# Endurence.net
KiCad netlist of a schematic drawn in Altium Designer
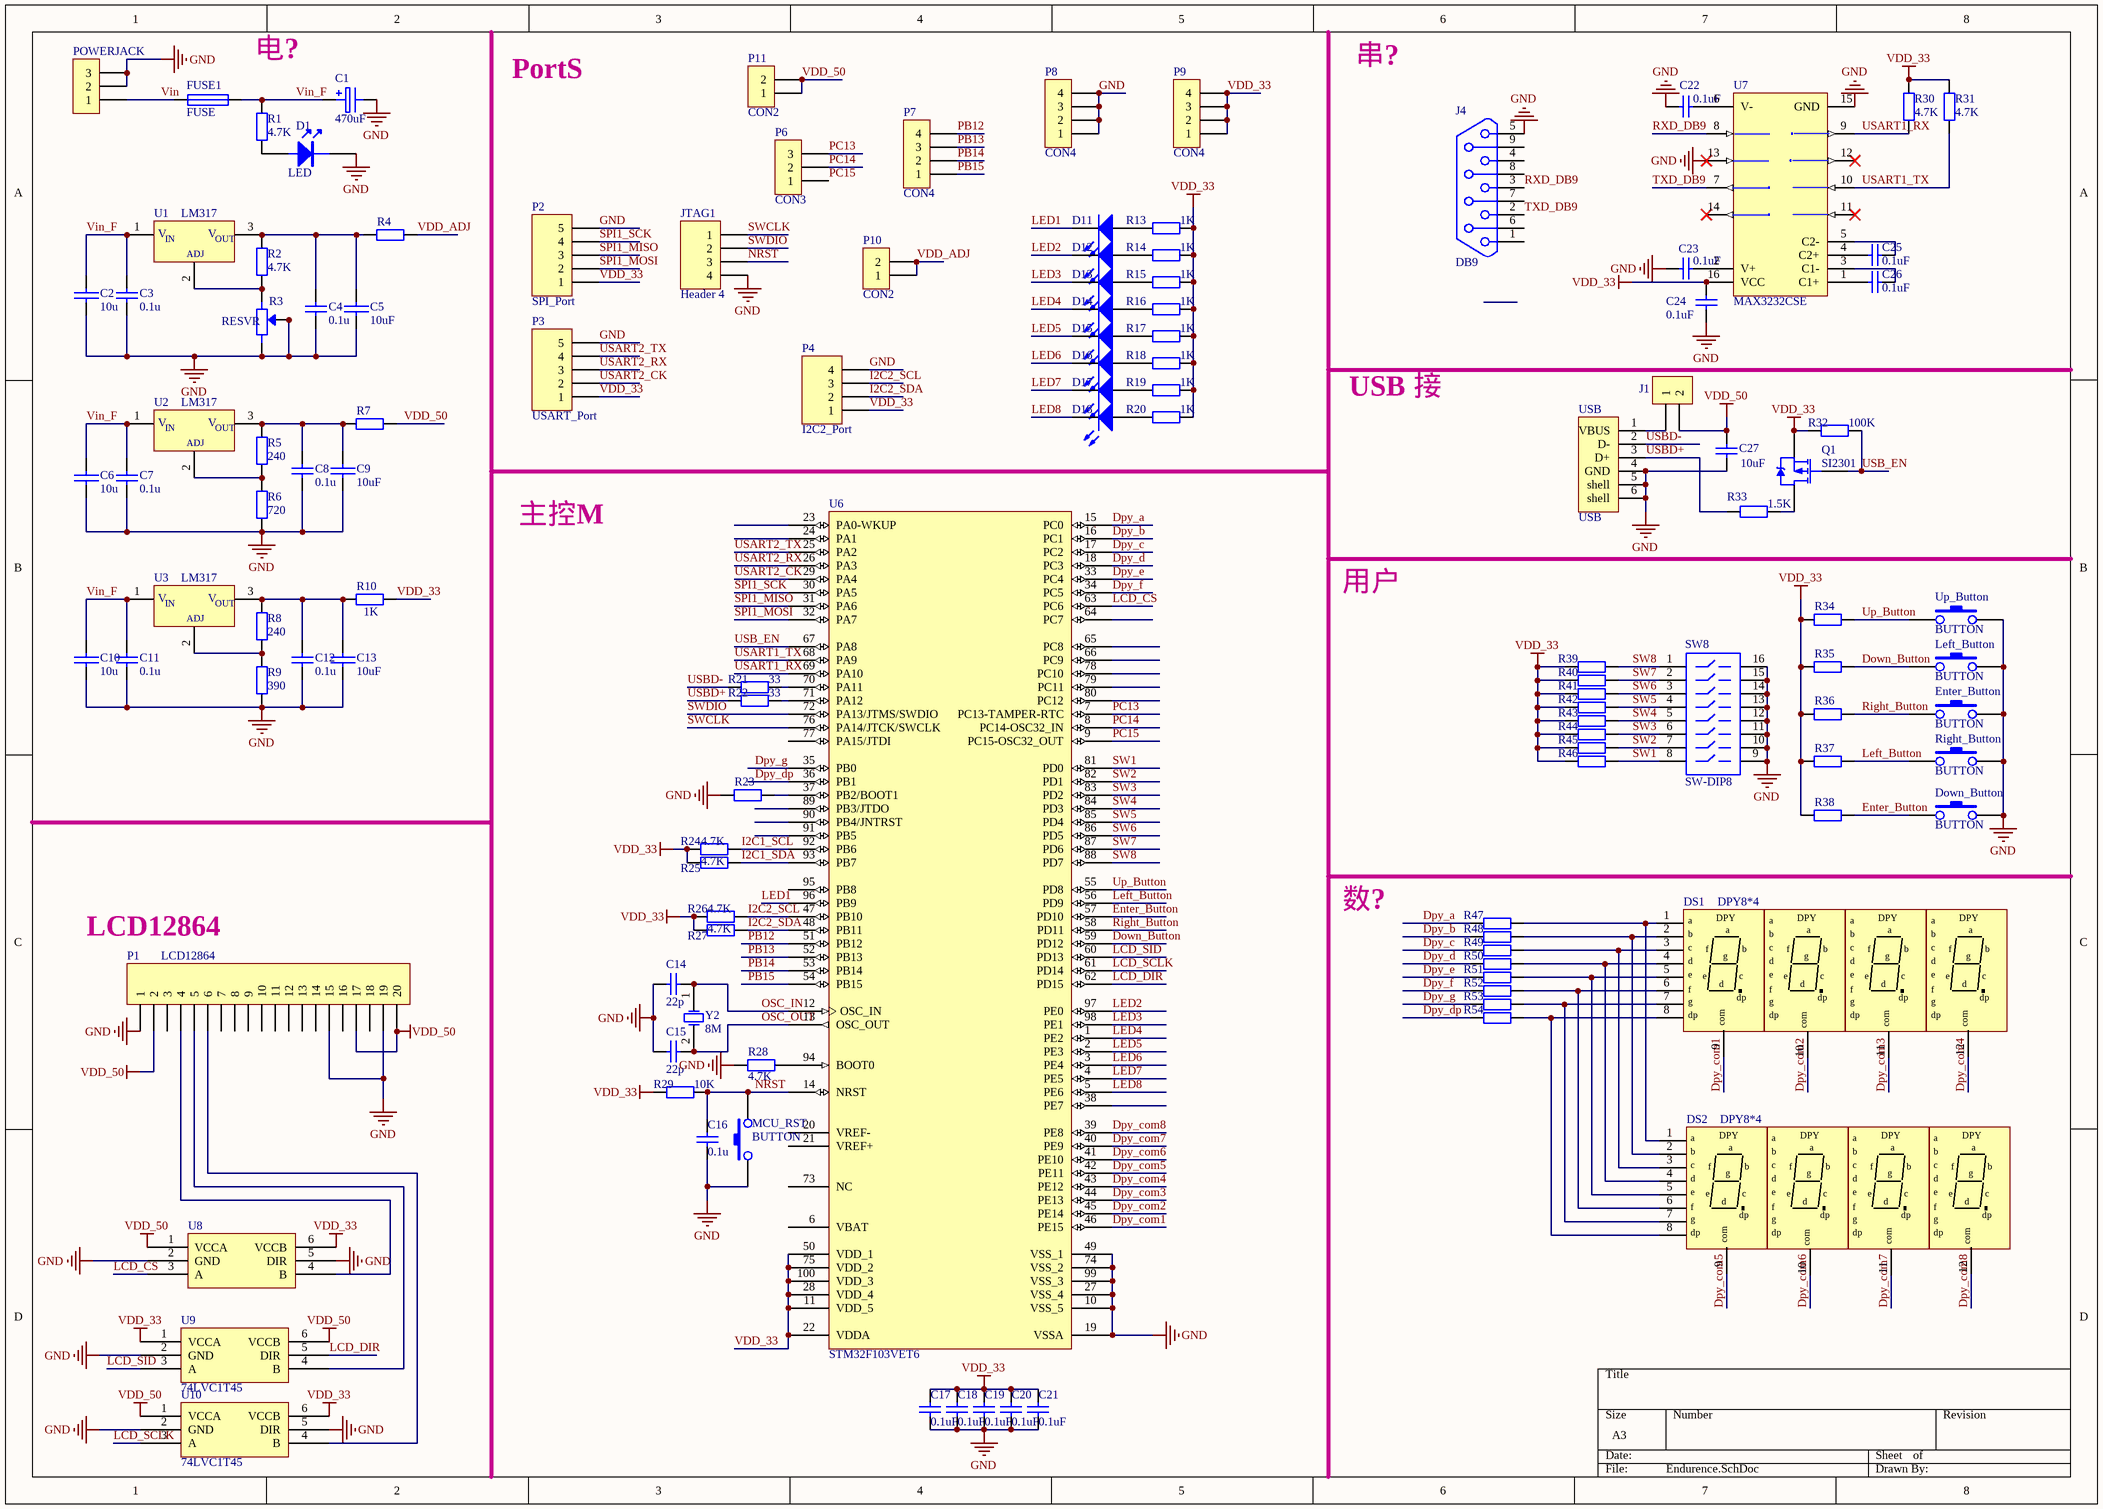
[diagram p0: Endurence.SchDoc]

(export (version "E")
  (design (tool "Eeschema 10.0.6"))
  (components
    (comp (ref "C1") (value "470uF") (footprint "MYRB.2/.4") (libsource (lib "yanschlib") (part "ELECTRO1")))
    (comp (ref "C2") (value "10u") (footprint "0805") (libsource (lib "YPF") (part "CAP")))
    (comp (ref "C3")
      (value "0.1u")
      (footprint "0805")
      (description "Capacitor")
      (fields (field (name "Comment") "0.1uF") (field (name "PUBLISHER") "Altium Limited"))
      (libsource (lib "Miscellaneous Devices") (part "Cap"))
    )
    (comp (ref "C4")
      (value "0.1u")
      (footprint "0805")
      (description "Capacitor")
      (fields (field (name "Comment") "0.1uF") (field (name "PUBLISHER") "Altium Limited"))
      (libsource (lib "Miscellaneous Devices") (part "Cap"))
    )
    (comp (ref "C5") (value "10uF") (footprint "0805") (libsource (lib "YPF") (part "CAP")))
    (comp (ref "C6") (value "10u") (footprint "0805") (libsource (lib "YPF") (part "CAP")))
    (comp (ref "C7")
      (value "0.1u")
      (footprint "0805")
      (description "Capacitor")
      (fields (field (name "Comment") "0.1uF") (field (name "PUBLISHER") "Altium Limited"))
      (libsource (lib "Miscellaneous Devices") (part "Cap"))
    )
    (comp (ref "C8")
      (value "0.1u")
      (footprint "0805")
      (description "Capacitor")
      (fields (field (name "Comment") "0.1uF") (field (name "PUBLISHER") "Altium Limited"))
      (libsource (lib "Miscellaneous Devices") (part "Cap"))
    )
    (comp (ref "C9") (value "10uF") (footprint "0805") (libsource (lib "YPF") (part "CAP")))
    (comp (ref "C10") (value "10u") (footprint "0805") (libsource (lib "YPF") (part "CAP")))
    (comp (ref "C11")
      (value "0.1u")
      (footprint "0805")
      (description "Capacitor")
      (fields (field (name "Comment") "0.1uF") (field (name "PUBLISHER") "Altium Limited"))
      (libsource (lib "Miscellaneous Devices") (part "Cap"))
    )
    (comp (ref "C12")
      (value "0.1u")
      (footprint "0805")
      (description "Capacitor")
      (fields (field (name "Comment") "0.1uF") (field (name "PUBLISHER") "Altium Limited"))
      (libsource (lib "Miscellaneous Devices") (part "Cap"))
    )
    (comp (ref "C13") (value "10uF") (footprint "0805") (libsource (lib "YPF") (part "CAP")))
    (comp (ref "C14")
      (value "22p")
      (footprint "0805")
      (description "Capacitor")
      (fields (field (name "Comment") "20pF") (field (name "PUBLISHER") "Altium Limited"))
      (libsource (lib "Miscellaneous Devices") (part "Cap"))
    )
    (comp (ref "C15")
      (value "22p")
      (footprint "0805")
      (description "Capacitor")
      (fields (field (name "Comment") "20pF") (field (name "PUBLISHER") "Altium Limited"))
      (libsource (lib "Miscellaneous Devices") (part "Cap"))
    )
    (comp (ref "C16")
      (value "0.1u")
      (footprint "0805")
      (description "Capacitor")
      (fields (field (name "Comment") "0.1uF") (field (name "PUBLISHER") "Altium Limited"))
      (libsource (lib "Miscellaneous Devices") (part "Cap"))
    )
    (comp (ref "C17")
      (value "0.1uF")
      (footprint "0805")
      (description "Capacitor")
      (fields (field (name "PUBLISHER") "Altium Limited"))
      (libsource (lib "Miscellaneous Devices") (part "Cap"))
    )
    (comp (ref "C18")
      (value "0.1uF")
      (footprint "0805")
      (description "Capacitor")
      (fields (field (name "PUBLISHER") "Altium Limited"))
      (libsource (lib "Miscellaneous Devices") (part "Cap"))
    )
    (comp (ref "C19")
      (value "0.1uF")
      (footprint "0805")
      (description "Capacitor")
      (fields (field (name "PUBLISHER") "Altium Limited"))
      (libsource (lib "Miscellaneous Devices") (part "Cap"))
    )
    (comp (ref "C20")
      (value "0.1uF")
      (footprint "0805")
      (description "Capacitor")
      (fields (field (name "PUBLISHER") "Altium Limited"))
      (libsource (lib "Miscellaneous Devices") (part "Cap"))
    )
    (comp (ref "C21")
      (value "0.1uF")
      (footprint "0805")
      (description "Capacitor")
      (fields (field (name "PUBLISHER") "Altium Limited"))
      (libsource (lib "Miscellaneous Devices") (part "Cap"))
    )
    (comp (ref "C22")
      (value "0.1uF")
      (footprint "0805")
      (description "Capacitor")
      (libsource (lib "通用元件库") (part "C"))
    )
    (comp (ref "C23")
      (value "0.1uF")
      (footprint "0805")
      (description "Capacitor")
      (libsource (lib "通用元件库") (part "C"))
    )
    (comp (ref "C24")
      (value "0.1uF")
      (footprint "0805")
      (description "Capacitor")
      (libsource (lib "通用元件库") (part "C"))
    )
    (comp (ref "C25")
      (value "0.1uF")
      (footprint "0805")
      (description "Capacitor")
      (libsource (lib "通用元件库") (part "C"))
    )
    (comp (ref "C26")
      (value "0.1uF")
      (footprint "0805")
      (description "Capacitor")
      (libsource (lib "通用元件库") (part "C"))
    )
    (comp (ref "C27")
      (value "10uF")
      (footprint "0805")
      (description "Capacitor")
      (fields (field (name "PUBLISHER") "Altium Limited"))
      (libsource (lib "Miscellaneous Devices") (part "Cap"))
    )
    (comp (ref "D1") (value "LED") (footprint "0805") (libsource (lib "FM_SCH") (part "LED")))
    (comp (ref "D11")
      (value "LED2")
      (footprint "0805")
      (description "Typical RED, GREEN, YELLOW, AMBER GaAs LED")
      (fields (field (name "PUBLISHER") "Altium Limited"))
      (libsource (lib "Miscellaneous Devices") (part "LED2"))
    )
    (comp (ref "D12")
      (value "LED2")
      (footprint "0805")
      (description "Typical RED, GREEN, YELLOW, AMBER GaAs LED")
      (fields (field (name "PUBLISHER") "Altium Limited"))
      (libsource (lib "Miscellaneous Devices") (part "LED2"))
    )
    (comp (ref "D13")
      (value "LED2")
      (footprint "0805")
      (description "Typical RED, GREEN, YELLOW, AMBER GaAs LED")
      (fields (field (name "PUBLISHER") "Altium Limited"))
      (libsource (lib "Miscellaneous Devices") (part "LED2"))
    )
    (comp (ref "D14")
      (value "LED2")
      (footprint "0805")
      (description "Typical RED, GREEN, YELLOW, AMBER GaAs LED")
      (fields (field (name "PUBLISHER") "Altium Limited"))
      (libsource (lib "Miscellaneous Devices") (part "LED2"))
    )
    (comp (ref "D15")
      (value "LED2")
      (footprint "0805")
      (description "Typical RED, GREEN, YELLOW, AMBER GaAs LED")
      (fields (field (name "PUBLISHER") "Altium Limited"))
      (libsource (lib "Miscellaneous Devices") (part "LED2"))
    )
    (comp (ref "D16")
      (value "LED2")
      (footprint "0805")
      (description "Typical RED, GREEN, YELLOW, AMBER GaAs LED")
      (fields (field (name "PUBLISHER") "Altium Limited"))
      (libsource (lib "Miscellaneous Devices") (part "LED2"))
    )
    (comp (ref "D17")
      (value "LED2")
      (footprint "0805")
      (description "Typical RED, GREEN, YELLOW, AMBER GaAs LED")
      (fields (field (name "PUBLISHER") "Altium Limited"))
      (libsource (lib "Miscellaneous Devices") (part "LED2"))
    )
    (comp (ref "D18")
      (value "LED2")
      (footprint "0805")
      (description "Typical RED, GREEN, YELLOW, AMBER GaAs LED")
      (fields (field (name "PUBLISHER") "Altium Limited"))
      (libsource (lib "Miscellaneous Devices") (part "LED2"))
    )
    (comp (ref "Down_Button")
      (value "BUTTON")
      (footprint "BUTTON-S")
      (description "乒乓球按键（压下后接通，松开自动断开），较大按键尺寸12mmX12mm选用BUTTON-L封装，较小尺寸6mmX6mm选用BUTTON-S封装")
      (libsource (lib "fm274") (part "BUTTON"))
    )
    (comp (ref "DS1")
      (value "DPY8*4")
      (footprint "DYP8*4")
      (libsource (lib "Schlib1") (part "DPY_7-SEG_DP_4"))
    )
    (comp (ref "DS2")
      (value "DPY8*4")
      (footprint "DYP8*4")
      (libsource (lib "Schlib1") (part "DPY_7-SEG_DP_4"))
    )
    (comp (ref "Enter_Button")
      (value "BUTTON")
      (footprint "BUTTON-S")
      (description "乒乓球按键（压下后接通，松开自动断开），较大按键尺寸12mmX12mm选用BUTTON-L封装，较小尺寸6mmX6mm选用BUTTON-S封装")
      (libsource (lib "fm274") (part "BUTTON"))
    )
    (comp (ref "FUSE1") (value "FUSE") (footprint "FUSE") (libsource (lib "YPF") (part "FUSE")))
    (comp (ref "J1")
      (value "CON2")
      (footprint "SIP2")
      (description "Connector")
      (libsource (lib "") (part "CON2_1"))
    )
    (comp (ref "J4")
      (value "DB9")
      (footprint "DB9")
      (description "标准DB9芯连接器，多用于串口连接，使用母型接口DB9RA/F,公型接口DB9RA/M")
      (libsource (lib "FM_SCH") (part "DB9"))
    )
    (comp (ref "JTAG1")
      (value "Header 4")
      (footprint "HDR1X4")
      (description "Header, 4-Pin")
      (fields (field (name "PUBLISHER") "Altium Limited"))
      (libsource (lib "") (part "Header 4_1"))
    )
    (comp (ref "Left_Button")
      (value "BUTTON")
      (footprint "BUTTON-S")
      (description "乒乓球按键（压下后接通，松开自动断开），较大按键尺寸12mmX12mm选用BUTTON-L封装，较小尺寸6mmX6mm选用BUTTON-S封装")
      (libsource (lib "fm274") (part "BUTTON"))
    )
    (comp (ref "MCU_RST")
      (value "BUTTON")
      (footprint "BUTTON-S")
      (description "Button")
      (libsource (lib "fm274") (part "BUTTON"))
    )
    (comp (ref "P1")
      (value "LCD12864")
      (footprint "LCD12864")
      (description "Header, 20-Pin")
      (fields (field (name "PUBLISHER") "Altium Limited"))
      (libsource (lib "Miscellaneous Connectors") (part "Header 20"))
    )
    (comp (ref "P2")
      (value "SPI_Port")
      (footprint "HDR1X5")
      (description "Header, 5-Pin")
      (fields (field (name "PUBLISHER") "Altium Limited"))
      (libsource (lib "Miscellaneous Connectors") (part "Header 5"))
    )
    (comp (ref "P3")
      (value "USART_Port")
      (footprint "HDR1X5")
      (description "Header, 5-Pin")
      (fields (field (name "PUBLISHER") "Altium Limited"))
      (libsource (lib "Miscellaneous Connectors") (part "Header 5"))
    )
    (comp (ref "P4")
      (value "I2C2_Port")
      (footprint "HDR1X4")
      (description "Header, 4-Pin")
      (fields (field (name "PUBLISHER") "Altium Limited"))
      (libsource (lib "Miscellaneous Connectors") (part "Header 4"))
    )
    (comp (ref "P6")
      (value "CON3")
      (footprint "SIP3")
      (description "Connector")
      (libsource (lib "YPF") (part "CON3"))
    )
    (comp (ref "P7")
      (value "CON4")
      (footprint "SIP4")
      (description "Connector")
      (libsource (lib "YPF") (part "CON4"))
    )
    (comp (ref "P8")
      (value "CON4")
      (footprint "SIP4")
      (description "Connector")
      (libsource (lib "YPF") (part "CON4"))
    )
    (comp (ref "P9")
      (value "CON4")
      (footprint "SIP4")
      (description "Connector")
      (libsource (lib "YPF") (part "CON4"))
    )
    (comp (ref "P10")
      (value "CON2")
      (footprint "SIP2")
      (description "Connector")
      (libsource (lib "YPF") (part "CON2"))
    )
    (comp (ref "P11")
      (value "CON2")
      (footprint "SIP2")
      (description "Connector")
      (libsource (lib "YPF") (part "CON2"))
    )
    (comp (ref "POWERJACK")
      (value "CON3")
      (footprint "POWERJACK")
      (description "Connector")
      (libsource (lib "YPF") (part "CON3"))
    )
    (comp (ref "Q1")
      (value "SI2301")
      (footprint "SOT-23-2301")
      (description "P-Channel Power MOSFET")
      (fields (field (name "PUBLISHER") "Altium Limited"))
      (libsource (lib "Miscellaneous Devices") (part "PMOS-2"))
    )
    (comp (ref "R1") (value "4.7K") (footprint "0805") (description "0805") (libsource (lib "") (part "R_2")))
    (comp (ref "R2") (value "4.7K") (footprint "0805") (description "0805") (libsource (lib "") (part "R_2")))
    (comp (ref "R3")
      (value "RESVR")
      (footprint "SIP3")
      (description "Potentiometer")
      (libsource (lib "Schlib1") (part "RESVR"))
    )
    (comp (ref "R4")
      (value "1K")
      (footprint "0805")
      (description "Resistor")
      (fields (field (name "PUBLISHER") "Altium Limited"))
      (libsource (lib "Miscellaneous Devices") (part "Res2"))
    )
    (comp (ref "R5") (value "240") (footprint "0805") (description "0805") (libsource (lib "") (part "R_2")))
    (comp (ref "R6")
      (value "720")
      (footprint "0805")
      (description "0805")
      (libsource (lib "通用元件库") (part "R"))
    )
    (comp (ref "R7")
      (value "1K")
      (footprint "0805")
      (description "Resistor")
      (fields (field (name "PUBLISHER") "Altium Limited"))
      (libsource (lib "Miscellaneous Devices") (part "Res2"))
    )
    (comp (ref "R8") (value "240") (footprint "0805") (description "0805") (libsource (lib "") (part "R_2")))
    (comp (ref "R9")
      (value "390")
      (footprint "0805")
      (description "0805")
      (libsource (lib "通用元件库") (part "R"))
    )
    (comp (ref "R10")
      (value "1K")
      (footprint "0805")
      (description "Resistor")
      (fields (field (name "PUBLISHER") "Altium Limited"))
      (libsource (lib "Miscellaneous Devices") (part "Res2"))
    )
    (comp (ref "R13")
      (value "1K")
      (footprint "0805")
      (description "Resistor")
      (fields (field (name "PUBLISHER") "Altium Limited"))
      (libsource (lib "Miscellaneous Devices") (part "Res2"))
    )
    (comp (ref "R14")
      (value "1K")
      (footprint "0805")
      (description "Resistor")
      (fields (field (name "PUBLISHER") "Altium Limited"))
      (libsource (lib "") (part "Res2_1"))
    )
    (comp (ref "R15")
      (value "1K")
      (footprint "0805")
      (description "Resistor")
      (fields (field (name "PUBLISHER") "Altium Limited"))
      (libsource (lib "Miscellaneous Devices") (part "Res2"))
    )
    (comp (ref "R16")
      (value "1K")
      (footprint "0805")
      (description "Resistor")
      (fields (field (name "PUBLISHER") "Altium Limited"))
      (libsource (lib "Miscellaneous Devices") (part "Res2"))
    )
    (comp (ref "R17")
      (value "1K")
      (footprint "0805")
      (description "Resistor")
      (fields (field (name "PUBLISHER") "Altium Limited"))
      (libsource (lib "Miscellaneous Devices") (part "Res2"))
    )
    (comp (ref "R18")
      (value "1K")
      (footprint "0805")
      (description "Resistor")
      (fields (field (name "PUBLISHER") "Altium Limited"))
      (libsource (lib "") (part "Res2_1"))
    )
    (comp (ref "R19")
      (value "1K")
      (footprint "0805")
      (description "Resistor")
      (fields (field (name "PUBLISHER") "Altium Limited"))
      (libsource (lib "Miscellaneous Devices") (part "Res2"))
    )
    (comp (ref "R20")
      (value "1K")
      (footprint "0805")
      (description "Resistor")
      (fields (field (name "PUBLISHER") "Altium Limited"))
      (libsource (lib "Miscellaneous Devices") (part "Res2"))
    )
    (comp (ref "R21")
      (value "33")
      (footprint "0805")
      (description "Resistor")
      (fields (field (name "PUBLISHER") "Altium Limited"))
      (libsource (lib "Miscellaneous Devices") (part "Res2"))
    )
    (comp (ref "R22")
      (value "33")
      (footprint "0805")
      (description "Resistor")
      (fields (field (name "PUBLISHER") "Altium Limited"))
      (libsource (lib "Miscellaneous Devices") (part "Res2"))
    )
    (comp (ref "R23")
      (value "4.7K")
      (footprint "0805")
      (description "0805")
      (libsource (lib "") (part "R_1"))
    )
    (comp (ref "R24")
      (value "4.7K")
      (footprint "0805")
      (description "0805")
      (libsource (lib "") (part "R_1"))
    )
    (comp (ref "R25")
      (value "4.7K")
      (footprint "0805")
      (description "0805")
      (libsource (lib "") (part "R_1"))
    )
    (comp (ref "R26")
      (value "4.7K")
      (footprint "0805")
      (description "0805")
      (libsource (lib "") (part "R_1"))
    )
    (comp (ref "R27")
      (value "4.7K")
      (footprint "0805")
      (description "0805")
      (libsource (lib "") (part "R_1"))
    )
    (comp (ref "R28")
      (value "4.7K")
      (footprint "0805")
      (description "0805")
      (libsource (lib "") (part "R_1"))
    )
    (comp (ref "R29")
      (value "10K")
      (footprint "0805")
      (description "Resistor")
      (fields (field (name "PUBLISHER") "Altium Limited"))
      (libsource (lib "Miscellaneous Devices") (part "Res2"))
    )
    (comp (ref "R30")
      (value "4.7K")
      (footprint "0805")
      (description "0805")
      (libsource (lib "通用元件库") (part "R"))
    )
    (comp (ref "R31")
      (value "4.7K")
      (footprint "0805")
      (description "0805")
      (libsource (lib "通用元件库") (part "R"))
    )
    (comp (ref "R32")
      (value "100K")
      (footprint "0805")
      (description "Resistor")
      (fields (field (name "PUBLISHER") "Altium Limited"))
      (libsource (lib "Miscellaneous Devices") (part "Res2"))
    )
    (comp (ref "R33")
      (value "1.5K")
      (footprint "0805")
      (description "Resistor")
      (fields (field (name "PUBLISHER") "Altium Limited"))
      (libsource (lib "Miscellaneous Devices") (part "Res2"))
    )
    (comp (ref "R34")
      (value "4.7K")
      (footprint "0805")
      (description "Resistor")
      (fields (field (name "PUBLISHER") "Altium Limited"))
      (libsource (lib "Miscellaneous Devices") (part "Res2"))
    )
    (comp (ref "R35")
      (value "4.7K")
      (footprint "0805")
      (description "Resistor")
      (fields (field (name "PUBLISHER") "Altium Limited"))
      (libsource (lib "Miscellaneous Devices") (part "Res2"))
    )
    (comp (ref "R36")
      (value "4.7K")
      (footprint "0805")
      (description "Resistor")
      (fields (field (name "PUBLISHER") "Altium Limited"))
      (libsource (lib "Miscellaneous Devices") (part "Res2"))
    )
    (comp (ref "R37")
      (value "4.7K")
      (footprint "0805")
      (description "Resistor")
      (fields (field (name "PUBLISHER") "Altium Limited"))
      (libsource (lib "Miscellaneous Devices") (part "Res2"))
    )
    (comp (ref "R38")
      (value "4.7K")
      (footprint "0805")
      (description "Resistor")
      (fields (field (name "PUBLISHER") "Altium Limited"))
      (libsource (lib "Miscellaneous Devices") (part "Res2"))
    )
    (comp (ref "R39")
      (value "4.7K")
      (footprint "0805")
      (description "Resistor")
      (fields (field (name "PUBLISHER") "Altium Limited"))
      (libsource (lib "Miscellaneous Devices") (part "Res2"))
    )
    (comp (ref "R40")
      (value "4.7K")
      (footprint "0805")
      (description "Resistor")
      (fields (field (name "PUBLISHER") "Altium Limited"))
      (libsource (lib "Miscellaneous Devices") (part "Res2"))
    )
    (comp (ref "R41")
      (value "4.7K")
      (footprint "0805")
      (description "Resistor")
      (fields (field (name "PUBLISHER") "Altium Limited"))
      (libsource (lib "Miscellaneous Devices") (part "Res2"))
    )
    (comp (ref "R42")
      (value "4.7K")
      (footprint "0805")
      (description "Resistor")
      (fields (field (name "PUBLISHER") "Altium Limited"))
      (libsource (lib "Miscellaneous Devices") (part "Res2"))
    )
    (comp (ref "R43")
      (value "4.7K")
      (footprint "0805")
      (description "Resistor")
      (fields (field (name "PUBLISHER") "Altium Limited"))
      (libsource (lib "Miscellaneous Devices") (part "Res2"))
    )
    (comp (ref "R44")
      (value "4.7K")
      (footprint "0805")
      (description "Resistor")
      (fields (field (name "PUBLISHER") "Altium Limited"))
      (libsource (lib "Miscellaneous Devices") (part "Res2"))
    )
    (comp (ref "R45")
      (value "4.7K")
      (footprint "0805")
      (description "Resistor")
      (fields (field (name "PUBLISHER") "Altium Limited"))
      (libsource (lib "Miscellaneous Devices") (part "Res2"))
    )
    (comp (ref "R46")
      (value "4.7K")
      (footprint "0805")
      (description "Resistor")
      (fields (field (name "PUBLISHER") "Altium Limited"))
      (libsource (lib "Miscellaneous Devices") (part "Res2"))
    )
    (comp (ref "R47")
      (value "1K")
      (footprint "0805")
      (description "Resistor")
      (fields (field (name "PUBLISHER") "Altium Limited"))
      (libsource (lib "Miscellaneous Devices") (part "Res2"))
    )
    (comp (ref "R48")
      (value "1K")
      (footprint "0805")
      (description "Resistor")
      (fields (field (name "PUBLISHER") "Altium Limited"))
      (libsource (lib "Miscellaneous Devices") (part "Res2"))
    )
    (comp (ref "R49")
      (value "1K")
      (footprint "0805")
      (description "Resistor")
      (fields (field (name "PUBLISHER") "Altium Limited"))
      (libsource (lib "Miscellaneous Devices") (part "Res2"))
    )
    (comp (ref "R50")
      (value "1K")
      (footprint "0805")
      (description "Resistor")
      (fields (field (name "PUBLISHER") "Altium Limited"))
      (libsource (lib "Miscellaneous Devices") (part "Res2"))
    )
    (comp (ref "R51")
      (value "1K")
      (footprint "0805")
      (description "Resistor")
      (fields (field (name "PUBLISHER") "Altium Limited"))
      (libsource (lib "Miscellaneous Devices") (part "Res2"))
    )
    (comp (ref "R52")
      (value "1K")
      (footprint "0805")
      (description "Resistor")
      (fields (field (name "PUBLISHER") "Altium Limited"))
      (libsource (lib "Miscellaneous Devices") (part "Res2"))
    )
    (comp (ref "R53")
      (value "1K")
      (footprint "0805")
      (description "Resistor")
      (fields (field (name "PUBLISHER") "Altium Limited"))
      (libsource (lib "Miscellaneous Devices") (part "Res2"))
    )
    (comp (ref "R54")
      (value "1K")
      (footprint "0805")
      (description "Resistor")
      (fields (field (name "PUBLISHER") "Altium Limited"))
      (libsource (lib "Miscellaneous Devices") (part "Res2"))
    )
    (comp (ref "Right_Button")
      (value "BUTTON")
      (footprint "BUTTON-S")
      (libsource (lib "fm274") (part "BUTTON"))
    )
    (comp (ref "SW8")
      (value "SW-DIP8")
      (footprint "SW8")
      (description "4009 Series DIP Switch, Raised actuator")
      (fields (field (name "PUBLISHER") "Altium Limited"))
      (libsource (lib "Miscellaneous Devices") (part "SW-DIP8"))
    )
    (comp (ref "U1")
      (value "LM317")
      (footprint "LM317")
      (description "3-Terminal Adjustable Positive Voltage Regulator")
      (libsource (lib "YPF") (part "LM317"))
    )
    (comp (ref "U2")
      (value "LM317")
      (footprint "LM317")
      (description "3-Terminal Adjustable Positive Voltage Regulator")
      (libsource (lib "YPF") (part "LM317"))
    )
    (comp (ref "U3")
      (value "LM317")
      (footprint "LM317")
      (description "3-Terminal Adjustable Positive Voltage Regulator")
      (libsource (lib "YPF") (part "LM317"))
    )
    (comp (ref "U6")
      (value "STM32F103VET6")
      (footprint "LQFP100")
      (description "STM32 ARM-based 32-bit MCU with 64 Kbytes Flash, 100-pin LQFP, Industrial Temperature")
      (fields (field (name "PUBLISHER") "Altium Limited"))
      (libsource (lib "YPF") (part "STM32F103V8T6"))
    )
    (comp (ref "U7")
      (value "MAX3232CSE")
      (footprint "SSOP16")
      (description "3.0V TO 5.5V, Low-Power, up to 1Mbps, True RS-232 Transceiver Using Four 0.1µF External Capacitor")
      (fields (field (name "PUBLISHER") "Altium Limited"))
      (libsource (lib "Maxim Communication Transceiver") (part "MAX3232CSE"))
    )
    (comp (ref "U8") (value "74LVC1T45") (footprint "74LVC1T45") (libsource (lib "YPF") (part "74LVC1T45")))
    (comp (ref "U9") (value "74LVC1T45") (footprint "74LVC1T45") (libsource (lib "YPF") (part "74LVC1T45")))
    (comp (ref "U10") (value "74LVC1T45") (footprint "74LVC1T45") (libsource (lib "YPF") (part "74LVC1T45")))
    (comp (ref "Up_Button")
      (value "BUTTON")
      (footprint "BUTTON-S")
      (description "乒乓球按键（压下后接通，松开自动断开），较大按键尺寸12mmX12mm选用BUTTON-L封装，较小尺寸6mmX6mm选用BUTTON-S封装")
      (libsource (lib "fm274") (part "BUTTON"))
    )
    (comp (ref "USB") (value "USB") (footprint "USB-B") (libsource (lib "USB") (part "USB")))
    (comp (ref "Y2")
      (value "8M")
      (footprint "XTAL-0.2")
      (description "Crystal Oscillator")
      (fields (field (name "PUBLISHER") "Altium Limited"))
      (libsource (lib "Miscellaneous Devices") (part "XTAL"))
    )
  )
  (nets
    (net (code "1") (name "/Down_Button") (class "Default")
      (node (ref "Left_Button") (pin "1") (pinfunction "1_1") (pintype "passive"))
      (node (ref "R35") (pin "2") (pinfunction "2_2") (pintype "passive"))
      (node (ref "U6") (pin "59") (pinfunction "PD12_59") (pintype "bidirectional"))
    )
    (net (code "2") (name "/Dpy_a") (class "Default")
      (node (ref "R47") (pin "1") (pinfunction "1_1") (pintype "passive"))
      (node (ref "U6") (pin "15") (pinfunction "PC0_15") (pintype "bidirectional"))
    )
    (net (code "3") (name "/Dpy_b") (class "Default")
      (node (ref "R48") (pin "1") (pinfunction "1_1") (pintype "passive"))
      (node (ref "U6") (pin "16") (pinfunction "PC1_16") (pintype "bidirectional"))
    )
    (net (code "4") (name "/Dpy_c") (class "Default")
      (node (ref "R49") (pin "1") (pinfunction "1_1") (pintype "passive"))
      (node (ref "U6") (pin "17") (pinfunction "PC2_17") (pintype "bidirectional"))
    )
    (net (code "5") (name "/Dpy_com1") (class "Default")
      (node (ref "DS1") (pin "9") (pinfunction "com1_9") (pintype "passive"))
      (node (ref "U6") (pin "46") (pinfunction "PE15_46") (pintype "bidirectional"))
    )
    (net (code "6") (name "/Dpy_com2") (class "Default")
      (node (ref "DS1") (pin "10") (pinfunction "com2_10") (pintype "passive"))
      (node (ref "U6") (pin "45") (pinfunction "PE14_45") (pintype "bidirectional"))
    )
    (net (code "7") (name "/Dpy_com3") (class "Default")
      (node (ref "DS1") (pin "11") (pinfunction "com3_11") (pintype "passive"))
      (node (ref "U6") (pin "44") (pinfunction "PE13_44") (pintype "bidirectional"))
    )
    (net (code "8") (name "/Dpy_com4") (class "Default")
      (node (ref "DS1") (pin "12") (pinfunction "com4_12") (pintype "passive"))
      (node (ref "U6") (pin "43") (pinfunction "PE12_43") (pintype "bidirectional"))
    )
    (net (code "9") (name "/Dpy_com5") (class "Default")
      (node (ref "DS2") (pin "9") (pinfunction "com1_9") (pintype "passive"))
      (node (ref "U6") (pin "42") (pinfunction "PE11_42") (pintype "bidirectional"))
    )
    (net (code "10") (name "/Dpy_com6") (class "Default")
      (node (ref "DS2") (pin "10") (pinfunction "com2_10") (pintype "passive"))
      (node (ref "U6") (pin "41") (pinfunction "PE10_41") (pintype "bidirectional"))
    )
    (net (code "11") (name "/Dpy_com7") (class "Default")
      (node (ref "DS2") (pin "11") (pinfunction "com3_11") (pintype "passive"))
      (node (ref "U6") (pin "40") (pinfunction "PE9_40") (pintype "bidirectional"))
    )
    (net (code "12") (name "/Dpy_com8") (class "Default")
      (node (ref "DS2") (pin "12") (pinfunction "com4_12") (pintype "passive"))
      (node (ref "U6") (pin "39") (pinfunction "PE8_39") (pintype "bidirectional"))
    )
    (net (code "13") (name "/Dpy_d") (class "Default")
      (node (ref "R50") (pin "1") (pinfunction "1_1") (pintype "passive"))
      (node (ref "U6") (pin "18") (pinfunction "PC3_18") (pintype "bidirectional"))
    )
    (net (code "14") (name "/Dpy_dp") (class "Default")
      (node (ref "R54") (pin "1") (pinfunction "1_1") (pintype "passive"))
      (node (ref "U6") (pin "36") (pinfunction "PB1_36") (pintype "bidirectional"))
    )
    (net (code "15") (name "/Dpy_e") (class "Default")
      (node (ref "R51") (pin "1") (pinfunction "1_1") (pintype "passive"))
      (node (ref "U6") (pin "33") (pinfunction "PC4_33") (pintype "bidirectional"))
    )
    (net (code "16") (name "/Dpy_f") (class "Default")
      (node (ref "R52") (pin "1") (pinfunction "1_1") (pintype "passive"))
      (node (ref "U6") (pin "34") (pinfunction "PC5_34") (pintype "bidirectional"))
    )
    (net (code "17") (name "/Dpy_g") (class "Default")
      (node (ref "R53") (pin "1") (pinfunction "1_1") (pintype "passive"))
      (node (ref "U6") (pin "35") (pinfunction "PB0_35") (pintype "bidirectional"))
    )
    (net (code "18") (name "/Enter_Button") (class "Default")
      (node (ref "Down_Button") (pin "1") (pinfunction "1_1") (pintype "passive"))
      (node (ref "R38") (pin "2") (pinfunction "2_2") (pintype "passive"))
      (node (ref "U6") (pin "57") (pinfunction "PD10_57") (pintype "bidirectional"))
    )
    (net (code "19") (name "/I2C1_SCL") (class "Default")
      (node (ref "R24") (pin "1") (pinfunction "1_1") (pintype "passive"))
      (node (ref "U6") (pin "92") (pinfunction "PB6_92") (pintype "bidirectional"))
    )
    (net (code "20") (name "/I2C1_SDA") (class "Default")
      (node (ref "R25") (pin "1") (pinfunction "1_1") (pintype "passive"))
      (node (ref "U6") (pin "93") (pinfunction "PB7_93") (pintype "bidirectional"))
    )
    (net (code "21") (name "/I2C2_SCL") (class "Default")
      (node (ref "P4") (pin "3") (pinfunction "3_3") (pintype "passive"))
      (node (ref "R26") (pin "1") (pinfunction "1_1") (pintype "passive"))
      (node (ref "U6") (pin "47") (pinfunction "PB10_47") (pintype "bidirectional"))
    )
    (net (code "22") (name "/I2C2_SDA") (class "Default")
      (node (ref "P4") (pin "2") (pinfunction "2_2") (pintype "passive"))
      (node (ref "R27") (pin "1") (pinfunction "1_1") (pintype "passive"))
      (node (ref "U6") (pin "48") (pinfunction "PB11_48") (pintype "bidirectional"))
    )
    (net (code "23") (name "/LCD_CS") (class "Default")
      (node (ref "U6") (pin "63") (pinfunction "PC6_63") (pintype "bidirectional"))
      (node (ref "U8") (pin "3") (pinfunction "A_3") (pintype "passive"))
    )
    (net (code "24") (name "/LCD_DIR") (class "Default")
      (node (ref "U6") (pin "62") (pinfunction "PD15_62") (pintype "bidirectional"))
      (node (ref "U9") (pin "5") (pinfunction "DIR_5") (pintype "passive"))
    )
    (net (code "25") (name "/LCD_SCLK") (class "Default")
      (node (ref "U10") (pin "3") (pinfunction "A_3") (pintype "passive"))
      (node (ref "U6") (pin "61") (pinfunction "PD14_61") (pintype "bidirectional"))
    )
    (net (code "26") (name "/LCD_SID") (class "Default")
      (node (ref "U6") (pin "60") (pinfunction "PD13_60") (pintype "bidirectional"))
      (node (ref "U9") (pin "3") (pinfunction "A_3") (pintype "passive"))
    )
    (net (code "27") (name "/LED1") (class "Default")
      (node (ref "D11") (pin "2") (pinfunction "K_2") (pintype "passive"))
      (node (ref "U6") (pin "96") (pinfunction "PB9_96") (pintype "bidirectional"))
    )
    (net (code "28") (name "/LED2") (class "Default")
      (node (ref "D12") (pin "2") (pinfunction "K_2") (pintype "passive"))
      (node (ref "U6") (pin "97") (pinfunction "PE0_97") (pintype "bidirectional"))
    )
    (net (code "29") (name "/LED3") (class "Default")
      (node (ref "D13") (pin "2") (pinfunction "K_2") (pintype "passive"))
      (node (ref "U6") (pin "98") (pinfunction "PE1_98") (pintype "bidirectional"))
    )
    (net (code "30") (name "/LED4") (class "Default")
      (node (ref "D14") (pin "2") (pinfunction "K_2") (pintype "passive"))
      (node (ref "U6") (pin "1") (pinfunction "PE2_1") (pintype "bidirectional"))
    )
    (net (code "31") (name "/LED5") (class "Default")
      (node (ref "D15") (pin "2") (pinfunction "K_2") (pintype "passive"))
      (node (ref "U6") (pin "2") (pinfunction "PE3_2") (pintype "bidirectional"))
    )
    (net (code "32") (name "/LED6") (class "Default")
      (node (ref "D16") (pin "2") (pinfunction "K_2") (pintype "passive"))
      (node (ref "U6") (pin "3") (pinfunction "PE4_3") (pintype "bidirectional"))
    )
    (net (code "33") (name "/LED7") (class "Default")
      (node (ref "D17") (pin "2") (pinfunction "K_2") (pintype "passive"))
      (node (ref "U6") (pin "4") (pinfunction "PE5_4") (pintype "bidirectional"))
    )
    (net (code "34") (name "/LED8") (class "Default")
      (node (ref "D18") (pin "2") (pinfunction "K_2") (pintype "passive"))
      (node (ref "U6") (pin "5") (pinfunction "PE6_5") (pintype "bidirectional"))
    )
    (net (code "35") (name "/Left_Button") (class "Default")
      (node (ref "R37") (pin "2") (pinfunction "2_2") (pintype "passive"))
      (node (ref "Right_Button") (pin "1") (pinfunction "1_1") (pintype "passive"))
      (node (ref "U6") (pin "56") (pinfunction "PD9_56") (pintype "bidirectional"))
    )
    (net (code "36") (name "/NRST") (class "Default")
      (node (ref "C16") (pin "2") (pinfunction "2_2") (pintype "passive"))
      (node (ref "JTAG1") (pin "3") (pinfunction "3_3") (pintype "passive"))
      (node (ref "MCU_RST") (pin "2") (pinfunction "2_2") (pintype "passive"))
      (node (ref "R29") (pin "2") (pinfunction "2_2") (pintype "passive"))
      (node (ref "U6") (pin "14") (pinfunction "NRST_14") (pintype "bidirectional"))
    )
    (net (code "37") (name "/OSC_IN") (class "Default")
      (node (ref "C14") (pin "1") (pinfunction "1_1") (pintype "passive"))
      (node (ref "U6") (pin "12") (pinfunction "OSC_IN_12") (pintype "input"))
      (node (ref "Y2") (pin "1") (pinfunction "OSC1_1") (pintype "passive"))
    )
    (net (code "38") (name "/OSC_OUT") (class "Default")
      (node (ref "C15") (pin "1") (pinfunction "1_1") (pintype "passive"))
      (node (ref "U6") (pin "13") (pinfunction "OSC_OUT_13") (pintype "output"))
      (node (ref "Y2") (pin "2") (pinfunction "OSC2_2") (pintype "passive"))
    )
    (net (code "39") (name "/PB12") (class "Default")
      (node (ref "P7") (pin "4") (pinfunction "4_4") (pintype "passive"))
      (node (ref "U6") (pin "51") (pinfunction "PB12_51") (pintype "bidirectional"))
    )
    (net (code "40") (name "/PB13") (class "Default")
      (node (ref "P7") (pin "3") (pinfunction "3_3") (pintype "passive"))
      (node (ref "U6") (pin "52") (pinfunction "PB13_52") (pintype "bidirectional"))
    )
    (net (code "41") (name "/PB14") (class "Default")
      (node (ref "P7") (pin "2") (pinfunction "2_2") (pintype "passive"))
      (node (ref "U6") (pin "53") (pinfunction "PB14_53") (pintype "bidirectional"))
    )
    (net (code "42") (name "/PB15") (class "Default")
      (node (ref "P7") (pin "1") (pinfunction "1_1") (pintype "passive"))
      (node (ref "U6") (pin "54") (pinfunction "PB15_54") (pintype "bidirectional"))
    )
    (net (code "43") (name "/PC13") (class "Default")
      (node (ref "P6") (pin "3") (pinfunction "3_3") (pintype "passive"))
      (node (ref "U6") (pin "7") (pinfunction "PC13-TAMPER-RTC_7") (pintype "bidirectional"))
    )
    (net (code "44") (name "/PC14") (class "Default")
      (node (ref "P6") (pin "2") (pinfunction "2_2") (pintype "passive"))
      (node (ref "U6") (pin "8") (pinfunction "PC14-OSC32_IN_8") (pintype "bidirectional"))
    )
    (net (code "45") (name "/PC15") (class "Default")
      (node (ref "P6") (pin "1") (pinfunction "1_1") (pintype "passive"))
      (node (ref "U6") (pin "9") (pinfunction "PC15-OSC32_OUT_9") (pintype "bidirectional"))
    )
    (net (code "46") (name "/RXD_DB9") (class "Default")
      (node (ref "J4") (pin "3") (pinfunction "3_3") (pintype "passive"))
      (node (ref "U7") (pin "8") (pinfunction "R2IN_8") (pintype "input"))
    )
    (net (code "47") (name "/Right_Button") (class "Default")
      (node (ref "Enter_Button") (pin "1") (pinfunction "1_1") (pintype "passive"))
      (node (ref "R36") (pin "2") (pinfunction "2_2") (pintype "passive"))
      (node (ref "U6") (pin "58") (pinfunction "PD11_58") (pintype "bidirectional"))
    )
    (net (code "48") (name "/SPI1_MISO") (class "Default")
      (node (ref "P2") (pin "3") (pinfunction "3_3") (pintype "passive"))
      (node (ref "U6") (pin "31") (pinfunction "PA6_31") (pintype "bidirectional"))
    )
    (net (code "49") (name "/SPI1_MOSI") (class "Default")
      (node (ref "P2") (pin "2") (pinfunction "2_2") (pintype "passive"))
      (node (ref "U6") (pin "32") (pinfunction "PA7_32") (pintype "bidirectional"))
    )
    (net (code "50") (name "/SPI1_SCK") (class "Default")
      (node (ref "P2") (pin "4") (pinfunction "4_4") (pintype "passive"))
      (node (ref "U6") (pin "30") (pinfunction "PA5_30") (pintype "bidirectional"))
    )
    (net (code "51") (name "/SW1") (class "Default")
      (node (ref "R46") (pin "2") (pinfunction "2_2") (pintype "passive"))
      (node (ref "SW8") (pin "8") (pinfunction "8_8") (pintype "passive"))
      (node (ref "U6") (pin "81") (pinfunction "PD0_81") (pintype "bidirectional"))
    )
    (net (code "52") (name "/SW2") (class "Default")
      (node (ref "R45") (pin "2") (pinfunction "2_2") (pintype "passive"))
      (node (ref "SW8") (pin "7") (pinfunction "7_7") (pintype "passive"))
      (node (ref "U6") (pin "82") (pinfunction "PD1_82") (pintype "bidirectional"))
    )
    (net (code "53") (name "/SW3") (class "Default")
      (node (ref "R44") (pin "2") (pinfunction "2_2") (pintype "passive"))
      (node (ref "SW8") (pin "6") (pinfunction "6_6") (pintype "passive"))
      (node (ref "U6") (pin "83") (pinfunction "PD2_83") (pintype "bidirectional"))
    )
    (net (code "54") (name "/SW4") (class "Default")
      (node (ref "R43") (pin "2") (pinfunction "2_2") (pintype "passive"))
      (node (ref "SW8") (pin "5") (pinfunction "5_5") (pintype "passive"))
      (node (ref "U6") (pin "84") (pinfunction "PD3_84") (pintype "bidirectional"))
    )
    (net (code "55") (name "/SW5") (class "Default")
      (node (ref "R42") (pin "2") (pinfunction "2_2") (pintype "passive"))
      (node (ref "SW8") (pin "4") (pinfunction "4_4") (pintype "passive"))
      (node (ref "U6") (pin "85") (pinfunction "PD4_85") (pintype "bidirectional"))
    )
    (net (code "56") (name "/SW6") (class "Default")
      (node (ref "R41") (pin "2") (pinfunction "2_2") (pintype "passive"))
      (node (ref "SW8") (pin "3") (pinfunction "3_3") (pintype "passive"))
      (node (ref "U6") (pin "86") (pinfunction "PD5_86") (pintype "bidirectional"))
    )
    (net (code "57") (name "/SW7") (class "Default")
      (node (ref "R40") (pin "2") (pinfunction "2_2") (pintype "passive"))
      (node (ref "SW8") (pin "2") (pinfunction "2_2") (pintype "passive"))
      (node (ref "U6") (pin "87") (pinfunction "PD6_87") (pintype "bidirectional"))
    )
    (net (code "58") (name "/SW8") (class "Default")
      (node (ref "R39") (pin "2") (pinfunction "2_2") (pintype "passive"))
      (node (ref "SW8") (pin "1") (pinfunction "1_1") (pintype "passive"))
      (node (ref "U6") (pin "88") (pinfunction "PD7_88") (pintype "bidirectional"))
    )
    (net (code "59") (name "/SWCLK") (class "Default")
      (node (ref "JTAG1") (pin "1") (pinfunction "1_1") (pintype "passive"))
      (node (ref "U6") (pin "76") (pinfunction "PA14/JTCK/SWCLK_76") (pintype "bidirectional"))
    )
    (net (code "60") (name "/SWDIO") (class "Default")
      (node (ref "JTAG1") (pin "2") (pinfunction "2_2") (pintype "passive"))
      (node (ref "U6") (pin "72") (pinfunction "PA13/JTMS/SWDIO_72") (pintype "bidirectional"))
    )
    (net (code "61") (name "/TXD_DB9") (class "Default")
      (node (ref "J4") (pin "2") (pinfunction "2_2") (pintype "passive"))
      (node (ref "U7") (pin "7") (pinfunction "T2OUT_7") (pintype "output"))
    )
    (net (code "62") (name "/USART1_RX") (class "Default")
      (node (ref "R30") (pin "1") (pinfunction "1_1") (pintype "passive"))
      (node (ref "U6") (pin "69") (pinfunction "PA10_69") (pintype "bidirectional"))
      (node (ref "U7") (pin "9") (pinfunction "R2OUT_9") (pintype "output"))
    )
    (net (code "63") (name "/USART1_TX") (class "Default")
      (node (ref "R31") (pin "1") (pinfunction "1_1") (pintype "passive"))
      (node (ref "U6") (pin "68") (pinfunction "PA9_68") (pintype "bidirectional"))
      (node (ref "U7") (pin "10") (pinfunction "T2IN_10") (pintype "input"))
    )
    (net (code "64") (name "/USART2_CK") (class "Default")
      (node (ref "P3") (pin "2") (pinfunction "2_2") (pintype "passive"))
      (node (ref "U6") (pin "29") (pinfunction "PA4_29") (pintype "bidirectional"))
    )
    (net (code "65") (name "/USART2_RX") (class "Default")
      (node (ref "P3") (pin "3") (pinfunction "3_3") (pintype "passive"))
      (node (ref "U6") (pin "26") (pinfunction "PA3_26") (pintype "bidirectional"))
    )
    (net (code "66") (name "/USART2_TX") (class "Default")
      (node (ref "P3") (pin "4") (pinfunction "4_4") (pintype "passive"))
      (node (ref "U6") (pin "25") (pinfunction "PA2_25") (pintype "bidirectional"))
    )
    (net (code "67") (name "/USBD+") (class "Default")
      (node (ref "R22") (pin "1") (pinfunction "1_1") (pintype "passive"))
      (node (ref "R33") (pin "1") (pinfunction "1_1") (pintype "passive"))
      (node (ref "USB") (pin "3") (pinfunction "D+_3") (pintype "passive"))
    )
    (net (code "68") (name "/USBD-") (class "Default")
      (node (ref "R21") (pin "1") (pinfunction "1_1") (pintype "passive"))
      (node (ref "USB") (pin "2") (pinfunction "D-_2") (pintype "passive"))
    )
    (net (code "69") (name "/USB_EN") (class "Default")
      (node (ref "Q1") (pin "1") (pinfunction "G_1") (pintype "passive"))
      (node (ref "R32") (pin "2") (pinfunction "2_2") (pintype "passive"))
      (node (ref "U6") (pin "67") (pinfunction "PA8_67") (pintype "bidirectional"))
    )
    (net (code "70") (name "/Up_Button") (class "Default")
      (node (ref "R34") (pin "2") (pinfunction "2_2") (pintype "passive"))
      (node (ref "U6") (pin "55") (pinfunction "PD8_55") (pintype "bidirectional"))
      (node (ref "Up_Button") (pin "1") (pinfunction "1_1") (pintype "passive"))
    )
    (net (code "71") (name "/VDD_ADJ") (class "Default")
      (node (ref "P10") (pin "1") (pinfunction "1_1") (pintype "passive"))
      (node (ref "P10") (pin "2") (pinfunction "2_2") (pintype "passive"))
      (node (ref "R4") (pin "2") (pinfunction "2_2") (pintype "passive"))
    )
    (net (code "72") (name "/Vin") (class "Default")
      (node (ref "FUSE1") (pin "1") (pinfunction "1_1") (pintype "passive"))
      (node (ref "POWERJACK") (pin "1") (pinfunction "1_1") (pintype "passive"))
    )
    (net (code "73") (name "/Vin_F") (class "Default")
      (node (ref "C1") (pin "1") (pintype "passive"))
      (node (ref "C10") (pin "1") (pinfunction "1_1") (pintype "passive"))
      (node (ref "C11") (pin "2") (pinfunction "2_2") (pintype "passive"))
      (node (ref "C2") (pin "1") (pinfunction "1_1") (pintype "passive"))
      (node (ref "C3") (pin "2") (pinfunction "2_2") (pintype "passive"))
      (node (ref "C6") (pin "1") (pinfunction "1_1") (pintype "passive"))
      (node (ref "C7") (pin "2") (pinfunction "2_2") (pintype "passive"))
      (node (ref "FUSE1") (pin "2") (pinfunction "2_2") (pintype "passive"))
      (node (ref "R1") (pin "1") (pinfunction "1_1") (pintype "passive"))
      (node (ref "U1") (pin "1") (pinfunction "VIN_1") (pintype "passive"))
      (node (ref "U2") (pin "1") (pinfunction "VIN_1") (pintype "passive"))
      (node (ref "U3") (pin "1") (pinfunction "VIN_1") (pintype "passive"))
    )
    (net (code "74") (name "GND") (class "Default")
      (node (ref "C1") (pin "2") (pintype "passive"))
      (node (ref "C10") (pin "2") (pinfunction "2_2") (pintype "passive"))
      (node (ref "C11") (pin "1") (pinfunction "1_1") (pintype "passive"))
      (node (ref "C12") (pin "1") (pinfunction "1_1") (pintype "passive"))
      (node (ref "C13") (pin "2") (pinfunction "2_2") (pintype "passive"))
      (node (ref "C14") (pin "2") (pinfunction "2_2") (pintype "passive"))
      (node (ref "C15") (pin "2") (pinfunction "2_2") (pintype "passive"))
      (node (ref "C16") (pin "1") (pinfunction "1_1") (pintype "passive"))
      (node (ref "C17") (pin "1") (pinfunction "1_1") (pintype "passive"))
      (node (ref "C18") (pin "1") (pinfunction "1_1") (pintype "passive"))
      (node (ref "C19") (pin "1") (pinfunction "1_1") (pintype "passive"))
      (node (ref "C2") (pin "2") (pinfunction "2_2") (pintype "passive"))
      (node (ref "C20") (pin "1") (pinfunction "1_1") (pintype "passive"))
      (node (ref "C21") (pin "1") (pinfunction "1_1") (pintype "passive"))
      (node (ref "C22") (pin "2") (pinfunction "2_2") (pintype "passive"))
      (node (ref "C23") (pin "2") (pinfunction "2_2") (pintype "passive"))
      (node (ref "C24") (pin "1") (pinfunction "1_1") (pintype "passive"))
      (node (ref "C27") (pin "1") (pinfunction "1_1") (pintype "passive"))
      (node (ref "C3") (pin "1") (pinfunction "1_1") (pintype "passive"))
      (node (ref "C4") (pin "1") (pinfunction "1_1") (pintype "passive"))
      (node (ref "C5") (pin "2") (pinfunction "2_2") (pintype "passive"))
      (node (ref "C6") (pin "2") (pinfunction "2_2") (pintype "passive"))
      (node (ref "C7") (pin "1") (pinfunction "1_1") (pintype "passive"))
      (node (ref "C8") (pin "1") (pinfunction "1_1") (pintype "passive"))
      (node (ref "C9") (pin "2") (pinfunction "2_2") (pintype "passive"))
      (node (ref "D1") (pin "2") (pinfunction "K_2") (pintype "passive"))
      (node (ref "Down_Button") (pin "2") (pinfunction "2_2") (pintype "passive"))
      (node (ref "Enter_Button") (pin "2") (pinfunction "2_2") (pintype "passive"))
      (node (ref "J4") (pin "5") (pinfunction "5_5") (pintype "passive"))
      (node (ref "JTAG1") (pin "4") (pinfunction "4_4") (pintype "passive"))
      (node (ref "Left_Button") (pin "2") (pinfunction "2_2") (pintype "passive"))
      (node (ref "MCU_RST") (pin "1") (pinfunction "1_1") (pintype "passive"))
      (node (ref "P1") (pin "1") (pinfunction "1_1") (pintype "passive"))
      (node (ref "P1") (pin "15") (pinfunction "15_15") (pintype "passive"))
      (node (ref "P1") (pin "19") (pinfunction "19_19") (pintype "passive"))
      (node (ref "P2") (pin "5") (pinfunction "5_5") (pintype "passive"))
      (node (ref "P3") (pin "5") (pinfunction "5_5") (pintype "passive"))
      (node (ref "P4") (pin "4") (pinfunction "4_4") (pintype "passive"))
      (node (ref "P8") (pin "1") (pinfunction "1_1") (pintype "passive"))
      (node (ref "P8") (pin "2") (pinfunction "2_2") (pintype "passive"))
      (node (ref "P8") (pin "3") (pinfunction "3_3") (pintype "passive"))
      (node (ref "P8") (pin "4") (pinfunction "4_4") (pintype "passive"))
      (node (ref "POWERJACK") (pin "2") (pinfunction "2_2") (pintype "passive"))
      (node (ref "POWERJACK") (pin "3") (pinfunction "3_3") (pintype "passive"))
      (node (ref "R23") (pin "2") (pinfunction "2_2") (pintype "passive"))
      (node (ref "R28") (pin "2") (pinfunction "2_2") (pintype "passive"))
      (node (ref "R3") (pin "2") (pinfunction "2_2") (pintype "passive"))
      (node (ref "R3") (pin "3") (pinfunction "W_3") (pintype "passive"))
      (node (ref "R6") (pin "1") (pinfunction "1_1") (pintype "passive"))
      (node (ref "R9") (pin "1") (pinfunction "1_1") (pintype "passive"))
      (node (ref "Right_Button") (pin "2") (pinfunction "2_2") (pintype "passive"))
      (node (ref "SW8") (pin "10") (pinfunction "10_10") (pintype "passive"))
      (node (ref "SW8") (pin "11") (pinfunction "11_11") (pintype "passive"))
      (node (ref "SW8") (pin "12") (pinfunction "12_12") (pintype "passive"))
      (node (ref "SW8") (pin "13") (pinfunction "13_13") (pintype "passive"))
      (node (ref "SW8") (pin "14") (pinfunction "14_14") (pintype "passive"))
      (node (ref "SW8") (pin "15") (pinfunction "15_15") (pintype "passive"))
      (node (ref "SW8") (pin "16") (pinfunction "16_16") (pintype "passive"))
      (node (ref "SW8") (pin "9") (pinfunction "9_9") (pintype "passive"))
      (node (ref "U10") (pin "2") (pinfunction "GND_2") (pintype "passive"))
      (node (ref "U10") (pin "5") (pinfunction "DIR_5") (pintype "passive"))
      (node (ref "U6") (pin "10") (pinfunction "VSS_5_10") (pintype "power_in"))
      (node (ref "U6") (pin "19") (pinfunction "VSSA_19") (pintype "power_in"))
      (node (ref "U6") (pin "27") (pinfunction "VSS_4_27") (pintype "power_in"))
      (node (ref "U6") (pin "49") (pinfunction "VSS_1_49") (pintype "power_in"))
      (node (ref "U6") (pin "74") (pinfunction "VSS_2_74") (pintype "power_in"))
      (node (ref "U6") (pin "99") (pinfunction "VSS_3_99") (pintype "power_in"))
      (node (ref "U7") (pin "13") (pinfunction "R1IN_13") (pintype "input"))
      (node (ref "U7") (pin "15") (pinfunction "GND_15") (pintype "power_in"))
      (node (ref "U8") (pin "2") (pinfunction "GND_2") (pintype "passive"))
      (node (ref "U8") (pin "5") (pinfunction "DIR_5") (pintype "passive"))
      (node (ref "U9") (pin "2") (pinfunction "GND_2") (pintype "passive"))
      (node (ref "USB") (pin "4") (pinfunction "GND_4") (pintype "passive"))
      (node (ref "USB") (pin "5") (pinfunction "shell_5") (pintype "passive"))
      (node (ref "USB") (pin "6") (pinfunction "shell_6") (pintype "passive"))
      (node (ref "Up_Button") (pin "2") (pinfunction "2_2") (pintype "passive"))
    )
    (net (code "75") (name "Net-(D1-A)") (class "Default")
      (node (ref "D1") (pin "1") (pinfunction "A_1") (pintype "passive"))
      (node (ref "R1") (pin "2") (pinfunction "2_2") (pintype "passive"))
    )
    (net (code "76") (name "Net-(D11-A)") (class "Default")
      (node (ref "D11") (pin "1") (pinfunction "A_1") (pintype "passive"))
      (node (ref "R13") (pin "1") (pinfunction "1_1") (pintype "passive"))
    )
    (net (code "77") (name "Net-(D12-A)") (class "Default")
      (node (ref "D12") (pin "1") (pinfunction "A_1") (pintype "passive"))
      (node (ref "R14") (pin "2") (pinfunction "2_2") (pintype "passive"))
    )
    (net (code "78") (name "Net-(D13-A)") (class "Default")
      (node (ref "D13") (pin "1") (pinfunction "A_1") (pintype "passive"))
      (node (ref "R15") (pin "1") (pinfunction "1_1") (pintype "passive"))
    )
    (net (code "79") (name "Net-(D14-A)") (class "Default")
      (node (ref "D14") (pin "1") (pinfunction "A_1") (pintype "passive"))
      (node (ref "R16") (pin "1") (pinfunction "1_1") (pintype "passive"))
    )
    (net (code "80") (name "Net-(D15-A)") (class "Default")
      (node (ref "D15") (pin "1") (pinfunction "A_1") (pintype "passive"))
      (node (ref "R17") (pin "1") (pinfunction "1_1") (pintype "passive"))
    )
    (net (code "81") (name "Net-(D16-A)") (class "Default")
      (node (ref "D16") (pin "1") (pinfunction "A_1") (pintype "passive"))
      (node (ref "R18") (pin "2") (pinfunction "2_2") (pintype "passive"))
    )
    (net (code "82") (name "Net-(D17-A)") (class "Default")
      (node (ref "D17") (pin "1") (pinfunction "A_1") (pintype "passive"))
      (node (ref "R19") (pin "1") (pinfunction "1_1") (pintype "passive"))
    )
    (net (code "83") (name "Net-(D18-A)") (class "Default")
      (node (ref "D18") (pin "1") (pinfunction "A_1") (pintype "passive"))
      (node (ref "R20") (pin "1") (pinfunction "1_1") (pintype "passive"))
    )
    (net (code "84") (name "Net-(DS1-a)") (class "Default")
      (node (ref "DS1") (pin "1") (pinfunction "a_1") (pintype "passive"))
      (node (ref "DS2") (pin "1") (pinfunction "a_1") (pintype "passive"))
      (node (ref "R47") (pin "2") (pinfunction "2_2") (pintype "passive"))
    )
    (net (code "85") (name "Net-(DS1-b)") (class "Default")
      (node (ref "DS1") (pin "2") (pinfunction "b_2") (pintype "passive"))
      (node (ref "DS2") (pin "2") (pinfunction "b_2") (pintype "passive"))
      (node (ref "R48") (pin "2") (pinfunction "2_2") (pintype "passive"))
    )
    (net (code "86") (name "Net-(DS1-c)") (class "Default")
      (node (ref "DS1") (pin "3") (pinfunction "c_3") (pintype "passive"))
      (node (ref "DS2") (pin "3") (pinfunction "c_3") (pintype "passive"))
      (node (ref "R49") (pin "2") (pinfunction "2_2") (pintype "passive"))
    )
    (net (code "87") (name "Net-(DS1-d)") (class "Default")
      (node (ref "DS1") (pin "4") (pinfunction "d_4") (pintype "passive"))
      (node (ref "DS2") (pin "4") (pinfunction "d_4") (pintype "passive"))
      (node (ref "R50") (pin "2") (pinfunction "2_2") (pintype "passive"))
    )
    (net (code "88") (name "Net-(DS1-dp)") (class "Default")
      (node (ref "DS1") (pin "8") (pinfunction "dp_8") (pintype "passive"))
      (node (ref "DS2") (pin "8") (pinfunction "dp_8") (pintype "passive"))
      (node (ref "R54") (pin "2") (pinfunction "2_2") (pintype "passive"))
    )
    (net (code "89") (name "Net-(DS1-e)") (class "Default")
      (node (ref "DS1") (pin "5") (pinfunction "e_5") (pintype "passive"))
      (node (ref "DS2") (pin "5") (pinfunction "e_5") (pintype "passive"))
      (node (ref "R51") (pin "2") (pinfunction "2_2") (pintype "passive"))
    )
    (net (code "90") (name "Net-(DS1-f)") (class "Default")
      (node (ref "DS1") (pin "6") (pinfunction "f_6") (pintype "passive"))
      (node (ref "DS2") (pin "6") (pinfunction "f_6") (pintype "passive"))
      (node (ref "R52") (pin "2") (pinfunction "2_2") (pintype "passive"))
    )
    (net (code "91") (name "Net-(DS1-g)") (class "Default")
      (node (ref "DS1") (pin "7") (pinfunction "g_7") (pintype "passive"))
      (node (ref "DS2") (pin "7") (pinfunction "g_7") (pintype "passive"))
      (node (ref "R53") (pin "2") (pinfunction "2_2") (pintype "passive"))
    )
    (net (code "92") (name "Net-(Q1-D)") (class "Default")
      (node (ref "Q1") (pin "2") (pinfunction "D_2") (pintype "passive"))
      (node (ref "R33") (pin "2") (pinfunction "2_2") (pintype "passive"))
    )
    (net (code "93") (name "Net-(U1-ADJ)") (class "Default")
      (node (ref "R2") (pin "2") (pinfunction "2_2") (pintype "passive"))
      (node (ref "R3") (pin "1") (pinfunction "1_1") (pintype "passive"))
      (node (ref "U1") (pin "2") (pinfunction "ADJ_2") (pintype "passive"))
    )
    (net (code "94") (name "Net-(U1-VOUT)") (class "Default")
      (node (ref "C4") (pin "2") (pinfunction "2_2") (pintype "passive"))
      (node (ref "C5") (pin "1") (pinfunction "1_1") (pintype "passive"))
      (node (ref "R2") (pin "1") (pinfunction "1_1") (pintype "passive"))
      (node (ref "R4") (pin "1") (pinfunction "1_1") (pintype "passive"))
      (node (ref "U1") (pin "3") (pinfunction "VOUT_3") (pintype "passive"))
    )
    (net (code "95") (name "Net-(U2-ADJ)") (class "Default")
      (node (ref "R5") (pin "2") (pinfunction "2_2") (pintype "passive"))
      (node (ref "R6") (pin "2") (pinfunction "2_2") (pintype "passive"))
      (node (ref "U2") (pin "2") (pinfunction "ADJ_2") (pintype "passive"))
    )
    (net (code "96") (name "Net-(U2-VOUT)") (class "Default")
      (node (ref "C8") (pin "2") (pinfunction "2_2") (pintype "passive"))
      (node (ref "C9") (pin "1") (pinfunction "1_1") (pintype "passive"))
      (node (ref "R5") (pin "1") (pinfunction "1_1") (pintype "passive"))
      (node (ref "R7") (pin "1") (pinfunction "1_1") (pintype "passive"))
      (node (ref "U2") (pin "3") (pinfunction "VOUT_3") (pintype "passive"))
    )
    (net (code "97") (name "Net-(U3-ADJ)") (class "Default")
      (node (ref "R8") (pin "2") (pinfunction "2_2") (pintype "passive"))
      (node (ref "R9") (pin "2") (pinfunction "2_2") (pintype "passive"))
      (node (ref "U3") (pin "2") (pinfunction "ADJ_2") (pintype "passive"))
    )
    (net (code "98") (name "Net-(U3-VOUT)") (class "Default")
      (node (ref "C12") (pin "2") (pinfunction "2_2") (pintype "passive"))
      (node (ref "C13") (pin "1") (pinfunction "1_1") (pintype "passive"))
      (node (ref "R10") (pin "1") (pinfunction "1_1") (pintype "passive"))
      (node (ref "R8") (pin "1") (pinfunction "1_1") (pintype "passive"))
      (node (ref "U3") (pin "3") (pinfunction "VOUT_3") (pintype "passive"))
    )
    (net (code "99") (name "Net-(U6-BOOT0)") (class "Default")
      (node (ref "R28") (pin "1") (pinfunction "1_1") (pintype "passive"))
      (node (ref "U6") (pin "94") (pinfunction "BOOT0_94") (pintype "input"))
    )
    (net (code "100") (name "Net-(U6-PA11)") (class "Default")
      (node (ref "R21") (pin "2") (pinfunction "2_2") (pintype "passive"))
      (node (ref "U6") (pin "70") (pinfunction "PA11_70") (pintype "bidirectional"))
    )
    (net (code "101") (name "Net-(U6-PA12)") (class "Default")
      (node (ref "R22") (pin "2") (pinfunction "2_2") (pintype "passive"))
      (node (ref "U6") (pin "71") (pinfunction "PA12_71") (pintype "bidirectional"))
    )
    (net (code "102") (name "Net-(U6-PB2{slash}BOOT1)") (class "Default")
      (node (ref "R23") (pin "1") (pinfunction "1_1") (pintype "passive"))
      (node (ref "U6") (pin "37") (pinfunction "PB2/BOOT1_37") (pintype "bidirectional"))
    )
    (net (code "103") (name "Net-(U7-C1+)") (class "Default")
      (node (ref "C26") (pin "2") (pinfunction "2_2") (pintype "passive"))
      (node (ref "U7") (pin "1") (pinfunction "C1+_1") (pintype "passive"))
    )
    (net (code "104") (name "Net-(U7-C1-)") (class "Default")
      (node (ref "C26") (pin "1") (pinfunction "1_1") (pintype "passive"))
      (node (ref "U7") (pin "3") (pinfunction "C1-_3") (pintype "passive"))
    )
    (net (code "105") (name "Net-(U7-C2+)") (class "Default")
      (node (ref "C25") (pin "2") (pinfunction "2_2") (pintype "passive"))
      (node (ref "U7") (pin "4") (pinfunction "C2+_4") (pintype "passive"))
    )
    (net (code "106") (name "Net-(U7-C2-)") (class "Default")
      (node (ref "C25") (pin "1") (pinfunction "1_1") (pintype "passive"))
      (node (ref "U7") (pin "5") (pinfunction "C2-_5") (pintype "passive"))
    )
    (net (code "107") (name "Net-(U7-V+)") (class "Default")
      (node (ref "C23") (pin "1") (pinfunction "1_1") (pintype "passive"))
      (node (ref "U7") (pin "2") (pinfunction "V+_2") (pintype "power_in"))
    )
    (net (code "108") (name "Net-(U7-V-)") (class "Default")
      (node (ref "C22") (pin "1") (pinfunction "1_1") (pintype "passive"))
      (node (ref "U7") (pin "6") (pinfunction "V-_6") (pintype "power_in"))
    )
    (net (code "109") (name "Net-(U8-B)") (class "Default")
      (node (ref "P1") (pin "4") (pinfunction "4_4") (pintype "passive"))
      (node (ref "U8") (pin "4") (pinfunction "B_4") (pintype "passive"))
    )
    (net (code "110") (name "Net-(U9-B)") (class "Default")
      (node (ref "P1") (pin "5") (pinfunction "5_5") (pintype "passive"))
      (node (ref "U9") (pin "4") (pinfunction "B_4") (pintype "passive"))
    )
    (net (code "111") (name "Net-(U10-B)") (class "Default")
      (node (ref "P1") (pin "6") (pinfunction "6_6") (pintype "passive"))
      (node (ref "U10") (pin "4") (pinfunction "B_4") (pintype "passive"))
    )
    (net (code "112") (name "Net-(USB-VBUS)") (class "Default")
      (node (ref "J1") (pin "1") (pinfunction "1_1") (pintype "passive"))
      (node (ref "USB") (pin "1") (pinfunction "VBUS_1") (pintype "passive"))
    )
    (net (code "113") (name "VDD_33") (class "Default")
      (node (ref "C17") (pin "2") (pinfunction "2_2") (pintype "passive"))
      (node (ref "C18") (pin "2") (pinfunction "2_2") (pintype "passive"))
      (node (ref "C19") (pin "2") (pinfunction "2_2") (pintype "passive"))
      (node (ref "C20") (pin "2") (pinfunction "2_2") (pintype "passive"))
      (node (ref "C21") (pin "2") (pinfunction "2_2") (pintype "passive"))
      (node (ref "C24") (pin "2") (pinfunction "2_2") (pintype "passive"))
      (node (ref "P2") (pin "1") (pinfunction "1_1") (pintype "passive"))
      (node (ref "P3") (pin "1") (pinfunction "1_1") (pintype "passive"))
      (node (ref "P4") (pin "1") (pinfunction "1_1") (pintype "passive"))
      (node (ref "P9") (pin "1") (pinfunction "1_1") (pintype "passive"))
      (node (ref "P9") (pin "2") (pinfunction "2_2") (pintype "passive"))
      (node (ref "P9") (pin "3") (pinfunction "3_3") (pintype "passive"))
      (node (ref "P9") (pin "4") (pinfunction "4_4") (pintype "passive"))
      (node (ref "Q1") (pin "3") (pinfunction "S_3") (pintype "passive"))
      (node (ref "R10") (pin "2") (pinfunction "2_2") (pintype "passive"))
      (node (ref "R13") (pin "2") (pinfunction "2_2") (pintype "passive"))
      (node (ref "R14") (pin "1") (pinfunction "1_1") (pintype "passive"))
      (node (ref "R15") (pin "2") (pinfunction "2_2") (pintype "passive"))
      (node (ref "R16") (pin "2") (pinfunction "2_2") (pintype "passive"))
      (node (ref "R17") (pin "2") (pinfunction "2_2") (pintype "passive"))
      (node (ref "R18") (pin "1") (pinfunction "1_1") (pintype "passive"))
      (node (ref "R19") (pin "2") (pinfunction "2_2") (pintype "passive"))
      (node (ref "R20") (pin "2") (pinfunction "2_2") (pintype "passive"))
      (node (ref "R24") (pin "2") (pinfunction "2_2") (pintype "passive"))
      (node (ref "R25") (pin "2") (pinfunction "2_2") (pintype "passive"))
      (node (ref "R26") (pin "2") (pinfunction "2_2") (pintype "passive"))
      (node (ref "R27") (pin "2") (pinfunction "2_2") (pintype "passive"))
      (node (ref "R29") (pin "1") (pinfunction "1_1") (pintype "passive"))
      (node (ref "R30") (pin "2") (pinfunction "2_2") (pintype "passive"))
      (node (ref "R31") (pin "2") (pinfunction "2_2") (pintype "passive"))
      (node (ref "R32") (pin "1") (pinfunction "1_1") (pintype "passive"))
      (node (ref "R34") (pin "1") (pinfunction "1_1") (pintype "passive"))
      (node (ref "R35") (pin "1") (pinfunction "1_1") (pintype "passive"))
      (node (ref "R36") (pin "1") (pinfunction "1_1") (pintype "passive"))
      (node (ref "R37") (pin "1") (pinfunction "1_1") (pintype "passive"))
      (node (ref "R38") (pin "1") (pinfunction "1_1") (pintype "passive"))
      (node (ref "R39") (pin "1") (pinfunction "1_1") (pintype "passive"))
      (node (ref "R40") (pin "1") (pinfunction "1_1") (pintype "passive"))
      (node (ref "R41") (pin "1") (pinfunction "1_1") (pintype "passive"))
      (node (ref "R42") (pin "1") (pinfunction "1_1") (pintype "passive"))
      (node (ref "R43") (pin "1") (pinfunction "1_1") (pintype "passive"))
      (node (ref "R44") (pin "1") (pinfunction "1_1") (pintype "passive"))
      (node (ref "R45") (pin "1") (pinfunction "1_1") (pintype "passive"))
      (node (ref "R46") (pin "1") (pinfunction "1_1") (pintype "passive"))
      (node (ref "U10") (pin "6") (pinfunction "VCCB_6") (pintype "passive"))
      (node (ref "U6") (pin "100") (pinfunction "VDD_3_100") (pintype "power_in"))
      (node (ref "U6") (pin "11") (pinfunction "VDD_5_11") (pintype "power_in"))
      (node (ref "U6") (pin "22") (pinfunction "VDDA_22") (pintype "power_in"))
      (node (ref "U6") (pin "28") (pinfunction "VDD_4_28") (pintype "power_in"))
      (node (ref "U6") (pin "50") (pinfunction "VDD_1_50") (pintype "power_in"))
      (node (ref "U6") (pin "75") (pinfunction "VDD_2_75") (pintype "power_in"))
      (node (ref "U7") (pin "16") (pinfunction "VCC_16") (pintype "power_in"))
      (node (ref "U8") (pin "6") (pinfunction "VCCB_6") (pintype "passive"))
      (node (ref "U9") (pin "1") (pinfunction "VCCA_1") (pintype "passive"))
    )
    (net (code "114") (name "VDD_50") (class "Default")
      (node (ref "C27") (pin "2") (pinfunction "2_2") (pintype "passive"))
      (node (ref "J1") (pin "2") (pinfunction "2_2") (pintype "passive"))
      (node (ref "P1") (pin "17") (pinfunction "17_17") (pintype "passive"))
      (node (ref "P1") (pin "2") (pinfunction "2_2") (pintype "passive"))
      (node (ref "P1") (pin "20") (pinfunction "20_20") (pintype "passive"))
      (node (ref "P11") (pin "1") (pinfunction "1_1") (pintype "passive"))
      (node (ref "P11") (pin "2") (pinfunction "2_2") (pintype "passive"))
      (node (ref "R7") (pin "2") (pinfunction "2_2") (pintype "passive"))
      (node (ref "U10") (pin "1") (pinfunction "VCCA_1") (pintype "passive"))
      (node (ref "U8") (pin "1") (pinfunction "VCCA_1") (pintype "passive"))
      (node (ref "U9") (pin "6") (pinfunction "VCCB_6") (pintype "passive"))
    )
    (net (code "115") (name "unconnected-(J4-Pad1)") (class "Default")
      (node (ref "J4") (pin "1") (pinfunction "1_1") (pintype "passive"))
    )
    (net (code "116") (name "unconnected-(J4-Pad4)") (class "Default")
      (node (ref "J4") (pin "4") (pinfunction "4_4") (pintype "passive"))
    )
    (net (code "117") (name "unconnected-(J4-Pad6)") (class "Default")
      (node (ref "J4") (pin "6") (pinfunction "6_6") (pintype "passive"))
    )
    (net (code "118") (name "unconnected-(J4-Pad7)") (class "Default")
      (node (ref "J4") (pin "7") (pinfunction "7_7") (pintype "passive"))
    )
    (net (code "119") (name "unconnected-(J4-Pad8)") (class "Default")
      (node (ref "J4") (pin "8") (pinfunction "8_8") (pintype "passive"))
    )
    (net (code "120") (name "unconnected-(J4-Pad9)") (class "Default")
      (node (ref "J4") (pin "9") (pinfunction "9_9") (pintype "passive"))
    )
    (net (code "121") (name "unconnected-(P1-Pad3)") (class "Default")
      (node (ref "P1") (pin "3") (pinfunction "3_3") (pintype "passive"))
    )
    (net (code "122") (name "unconnected-(P1-Pad7)") (class "Default")
      (node (ref "P1") (pin "7") (pinfunction "7_7") (pintype "passive"))
    )
    (net (code "123") (name "unconnected-(P1-Pad8)") (class "Default")
      (node (ref "P1") (pin "8") (pinfunction "8_8") (pintype "passive"))
    )
    (net (code "124") (name "unconnected-(P1-Pad9)") (class "Default")
      (node (ref "P1") (pin "9") (pinfunction "9_9") (pintype "passive"))
    )
    (net (code "125") (name "unconnected-(P1-Pad10)") (class "Default")
      (node (ref "P1") (pin "10") (pinfunction "10_10") (pintype "passive"))
    )
    (net (code "126") (name "unconnected-(P1-Pad11)") (class "Default")
      (node (ref "P1") (pin "11") (pinfunction "11_11") (pintype "passive"))
    )
    (net (code "127") (name "unconnected-(P1-Pad12)") (class "Default")
      (node (ref "P1") (pin "12") (pinfunction "12_12") (pintype "passive"))
    )
    (net (code "128") (name "unconnected-(P1-Pad13)") (class "Default")
      (node (ref "P1") (pin "13") (pinfunction "13_13") (pintype "passive"))
    )
    (net (code "129") (name "unconnected-(P1-Pad14)") (class "Default")
      (node (ref "P1") (pin "14") (pinfunction "14_14") (pintype "passive"))
    )
    (net (code "130") (name "unconnected-(P1-Pad16)") (class "Default")
      (node (ref "P1") (pin "16") (pinfunction "16_16") (pintype "passive"))
    )
    (net (code "131") (name "unconnected-(P1-Pad18)") (class "Default")
      (node (ref "P1") (pin "18") (pinfunction "18_18") (pintype "passive"))
    )
    (net (code "132") (name "unconnected-(U6-NC-Pad73)") (class "Default")
      (node (ref "U6") (pin "73") (pinfunction "NC_73") (pintype "passive"))
    )
    (net (code "133") (name "unconnected-(U6-PA0-WKUP-Pad23)") (class "Default")
      (node (ref "U6") (pin "23") (pinfunction "PA0-WKUP_23") (pintype "bidirectional"))
    )
    (net (code "134") (name "unconnected-(U6-PA1-Pad24)") (class "Default")
      (node (ref "U6") (pin "24") (pinfunction "PA1_24") (pintype "bidirectional"))
    )
    (net (code "135") (name "unconnected-(U6-PA15{slash}JTDI-Pad77)") (class "Default")
      (node (ref "U6") (pin "77") (pinfunction "PA15/JTDI_77") (pintype "bidirectional"))
    )
    (net (code "136") (name "unconnected-(U6-PB3{slash}JTDO-Pad89)") (class "Default")
      (node (ref "U6") (pin "89") (pinfunction "PB3/JTDO_89") (pintype "bidirectional"))
    )
    (net (code "137") (name "unconnected-(U6-PB4{slash}JNTRST-Pad90)") (class "Default")
      (node (ref "U6") (pin "90") (pinfunction "PB4/JNTRST_90") (pintype "bidirectional"))
    )
    (net (code "138") (name "unconnected-(U6-PB5-Pad91)") (class "Default")
      (node (ref "U6") (pin "91") (pinfunction "PB5_91") (pintype "bidirectional"))
    )
    (net (code "139") (name "unconnected-(U6-PB8-Pad95)") (class "Default")
      (node (ref "U6") (pin "95") (pinfunction "PB8_95") (pintype "bidirectional"))
    )
    (net (code "140") (name "unconnected-(U6-PC7-Pad64)") (class "Default")
      (node (ref "U6") (pin "64") (pinfunction "PC7_64") (pintype "bidirectional"))
    )
    (net (code "141") (name "unconnected-(U6-PC8-Pad65)") (class "Default")
      (node (ref "U6") (pin "65") (pinfunction "PC8_65") (pintype "bidirectional"))
    )
    (net (code "142") (name "unconnected-(U6-PC9-Pad66)") (class "Default")
      (node (ref "U6") (pin "66") (pinfunction "PC9_66") (pintype "bidirectional"))
    )
    (net (code "143") (name "unconnected-(U6-PC10-Pad78)") (class "Default")
      (node (ref "U6") (pin "78") (pinfunction "PC10_78") (pintype "bidirectional"))
    )
    (net (code "144") (name "unconnected-(U6-PC11-Pad79)") (class "Default")
      (node (ref "U6") (pin "79") (pinfunction "PC11_79") (pintype "bidirectional"))
    )
    (net (code "145") (name "unconnected-(U6-PC12-Pad80)") (class "Default")
      (node (ref "U6") (pin "80") (pinfunction "PC12_80") (pintype "bidirectional"))
    )
    (net (code "146") (name "unconnected-(U6-PE7-Pad38)") (class "Default")
      (node (ref "U6") (pin "38") (pinfunction "PE7_38") (pintype "bidirectional"))
    )
    (net (code "147") (name "unconnected-(U6-VBAT-Pad6)") (class "Default")
      (node (ref "U6") (pin "6") (pinfunction "VBAT_6") (pintype "power_in"))
    )
    (net (code "148") (name "unconnected-(U6-VREF+-Pad21)") (class "Default")
      (node (ref "U6") (pin "21") (pinfunction "VREF+_21") (pintype "power_in"))
    )
    (net (code "149") (name "unconnected-(U6-VREF--Pad20)") (class "Default")
      (node (ref "U6") (pin "20") (pinfunction "VREF-_20") (pintype "power_in"))
    )
    (net (code "150") (name "unconnected-(U7-R1OUT-Pad12)") (class "Default")
      (node (ref "U7") (pin "12") (pinfunction "R1OUT_12") (pintype "output+no_connect"))
    )
    (net (code "151") (name "unconnected-(U7-T1IN-Pad11)") (class "Default")
      (node (ref "U7") (pin "11") (pinfunction "T1IN_11") (pintype "input+no_connect"))
    )
    (net (code "152") (name "unconnected-(U7-T1OUT-Pad14)") (class "Default")
      (node (ref "U7") (pin "14") (pinfunction "T1OUT_14") (pintype "output+no_connect"))
    )
  )
)
